# PROC051C_LC_Filtering_Reference.net
KiCad netlist of a schematic drawn in Altium Designer
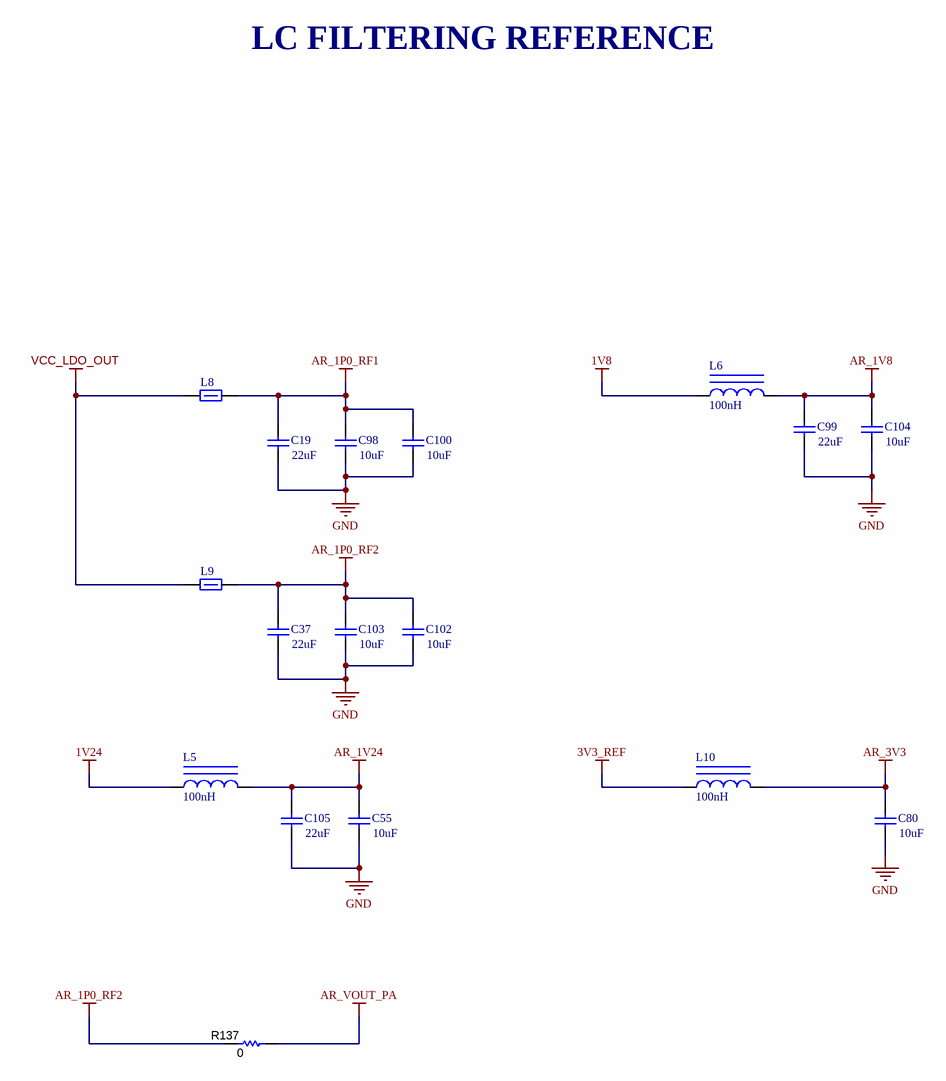
[diagram p0: PROC051C_LC_Filtering_Reference.SchDoc]

(export (version "E")
  (design (tool "Eeschema 10.0.6"))
  (components
    (comp (ref "C19")
      (value "CGA5L1X7R0J226M160AC")
      (footprint "1206_180")
      (description "CAP, CERM, 22 uF, 6.3 V, +/- 10%, X7R, AEC-Q200 Grade 1, 1206")
      (fields
        (field (name "MANUFACTURER") "TDK")
        (field (name "VALUEDISPLAYED") "22uF")
        (field (name "PUBLISHER") "Texas Instruments")
      )
      (libsource (lib "Altium Vault - TI") (part "Capacitor"))
    )
    (comp (ref "C37")
      (value "CGA5L1X7R0J226M160AC")
      (footprint "1206_180")
      (description "CAP, CERM, 22 uF, 6.3 V, +/- 10%, X7R, AEC-Q200 Grade 1, 1206")
      (fields
        (field (name "MANUFACTURER") "TDK")
        (field (name "VALUEDISPLAYED") "22uF")
        (field (name "PUBLISHER") "Texas Instruments")
      )
      (libsource (lib "Altium Vault - TI") (part "Capacitor"))
    )
    (comp (ref "C55")
      (value "GCM21BR71A106KE22L")
      (footprint "0805_HV")
      (description "CAP, CERM, 10 uF, 10 V, +/- 10%, X7R, 0805")
      (fields
        (field (name "MANUFACTURER") "MuRata")
        (field (name "VALUEDISPLAYED") "10uF")
        (field (name "PUBLISHER") "Texas Instruments")
      )
      (libsource (lib "Altium Vault - TI") (part "Capacitor"))
    )
    (comp (ref "C80")
      (value "GCM21BR71A106KE22L")
      (footprint "0805_HV")
      (description "CAP, CERM, 10 uF, 10 V, +/- 10%, X7R, 0805")
      (fields
        (field (name "MANUFACTURER") "MuRata")
        (field (name "VALUEDISPLAYED") "10uF")
        (field (name "PUBLISHER") "Texas Instruments")
      )
      (libsource (lib "Altium Vault - TI") (part "Capacitor"))
    )
    (comp (ref "C98")
      (value "GCM21BR71A106KE22L")
      (footprint "0805_HV")
      (description "CAP, CERM, 10 uF, 10 V, +/- 10%, X7R, 0805")
      (fields
        (field (name "MANUFACTURER") "MuRata")
        (field (name "VALUEDISPLAYED") "10uF")
        (field (name "PUBLISHER") "Texas Instruments")
      )
      (libsource (lib "Altium Vault - TI") (part "Capacitor"))
    )
    (comp (ref "C99")
      (value "CGA5L1X7R0J226M160AC")
      (footprint "1206_180")
      (description "CAP, CERM, 22 uF, 6.3 V, +/- 10%, X7R, AEC-Q200 Grade 1, 1206")
      (fields
        (field (name "MANUFACTURER") "TDK")
        (field (name "VALUEDISPLAYED") "22uF")
        (field (name "PUBLISHER") "Texas Instruments")
      )
      (libsource (lib "Altium Vault - TI") (part "Capacitor"))
    )
    (comp (ref "C100")
      (value "GCM21BR71A106KE22L")
      (footprint "0805_HV")
      (description "CAP, CERM, 10 uF, 10 V, +/- 10%, X7R, 0805")
      (fields
        (field (name "MANUFACTURER") "MuRata")
        (field (name "VALUEDISPLAYED") "10uF")
        (field (name "PUBLISHER") "Texas Instruments")
      )
      (libsource (lib "Altium Vault - TI") (part "Capacitor"))
    )
    (comp (ref "C102")
      (value "GCM21BR71A106KE22L")
      (footprint "0805_HV")
      (description "CAP, CERM, 10 uF, 10 V, +/- 10%, X7R, 0805")
      (fields
        (field (name "MANUFACTURER") "MuRata")
        (field (name "VALUEDISPLAYED") "10uF")
        (field (name "PUBLISHER") "Texas Instruments")
      )
      (libsource (lib "Altium Vault - TI") (part "Capacitor"))
    )
    (comp (ref "C103")
      (value "GCM21BR71A106KE22L")
      (footprint "0805_HV")
      (description "CAP, CERM, 10 uF, 10 V, +/- 10%, X7R, 0805")
      (fields
        (field (name "MANUFACTURER") "MuRata")
        (field (name "VALUEDISPLAYED") "10uF")
        (field (name "PUBLISHER") "Texas Instruments")
      )
      (libsource (lib "Altium Vault - TI") (part "Capacitor"))
    )
    (comp (ref "C104")
      (value "GCM21BR71A106KE22L")
      (footprint "0805_HV")
      (description "CAP, CERM, 10 uF, 10 V, +/- 10%, X7R, 0805")
      (fields
        (field (name "MANUFACTURER") "MuRata")
        (field (name "VALUEDISPLAYED") "10uF")
        (field (name "PUBLISHER") "Texas Instruments")
      )
      (libsource (lib "Altium Vault - TI") (part "Capacitor"))
    )
    (comp (ref "C105")
      (value "CGA5L1X7R0J226M160AC")
      (footprint "1206_180")
      (description "CAP, CERM, 22 uF, 6.3 V, +/- 10%, X7R, AEC-Q200 Grade 1, 1206")
      (fields
        (field (name "MANUFACTURER") "TDK")
        (field (name "VALUEDISPLAYED") "22uF")
        (field (name "PUBLISHER") "Texas Instruments")
      )
      (libsource (lib "Altium Vault - TI") (part "Capacitor"))
    )
    (comp (ref "L5")
      (value "NLCV32T-R10M-EFRD")
      (footprint "NLCV32")
      (description "Inductor, Wirewound, Ferrite, 100 nH, 2.85 A, 0.024 ohm, AEC-Q200 Grade 1, SMD")
      (fields (field (name "MANUFACTURER") "TDK") (field (name "VALUEDISPLAYED") "100nH"))
      (libsource (lib "Altium Vault - TI") (part "Inductor_Iron"))
    )
    (comp (ref "L6")
      (value "NLCV32T-R10M-EFRD")
      (footprint "NLCV32")
      (description "Inductor, Wirewound, Ferrite, 100 nH, 2.85 A, 0.024 ohm, AEC-Q200 Grade 1, SMD")
      (fields (field (name "MANUFACTURER") "TDK") (field (name "VALUEDISPLAYED") "100nH"))
      (libsource (lib "Altium Vault - TI") (part "Inductor_Iron"))
    )
    (comp (ref "L8")
      (value "BLM18KG121TH1D")
      (footprint "0603")
      (description "Ferrite Bead, 120 ohm @ 100 MHz, 1.9 A, 0603")
      (fields (field (name "MANUFACTURER") "MuRata"))
      (libsource (lib "Altium Vault - TI") (part "CMP-0077879-2"))
    )
    (comp (ref "L9")
      (value "BLM18KG121TH1D")
      (footprint "0603")
      (description "Ferrite Bead, 120 ohm @ 100 MHz, 1.9 A, 0603")
      (fields (field (name "MANUFACTURER") "MuRata"))
      (libsource (lib "Altium Vault - TI") (part "Ferrite_Bead"))
    )
    (comp (ref "L10")
      (value "NLCV32T-R10M-EFRD")
      (footprint "NLCV32")
      (description "Inductor, Wirewound, Ferrite, 100 nH, 2.85 A, 0.024 ohm, AEC-Q200 Grade 1, SMD")
      (fields (field (name "MANUFACTURER") "TDK") (field (name "VALUEDISPLAYED") "100nH"))
      (libsource (lib "Altium Vault - TI") (part "Inductor_Iron"))
    )
    (comp (ref "R137")
      (value "MCT06030Z0000ZP500")
      (footprint "0603")
      (description "RES, 0, 5%, 0.125 W, 0603")
      (fields
        (field (name "MANUFACTURER") "Vishay/Beyschlag")
        (field (name "VALUEDISPLAYED") "0")
        (field (name "PUBLISHER") "Texas Instruments")
      )
      (libsource (lib "Altium Vault - TI") (part "CMP-0025884-3"))
    )
  )
  (nets
    (net (code "1") (name "1V8") (class "Default")
      (node (ref "L6") (pin "1") (pinfunction "1_1") (pintype "passive"))
    )
    (net (code "2") (name "1V24") (class "Default")
      (node (ref "L5") (pin "1") (pinfunction "1_1") (pintype "passive"))
    )
    (net (code "3") (name "3V3_REF") (class "Default")
      (node (ref "L10") (pin "1") (pinfunction "1_1") (pintype "passive"))
    )
    (net (code "4") (name "AR_1P0_RF1") (class "Default")
      (node (ref "C100") (pin "1") (pinfunction "1_1") (pintype "passive"))
      (node (ref "C19") (pin "1") (pinfunction "1_1") (pintype "passive"))
      (node (ref "C98") (pin "1") (pinfunction "1_1") (pintype "passive"))
      (node (ref "L8") (pin "2") (pinfunction "2_2") (pintype "passive"))
    )
    (net (code "5") (name "AR_1P0_RF2") (class "Default")
      (node (ref "C102") (pin "1") (pinfunction "1_1") (pintype "passive"))
      (node (ref "C103") (pin "1") (pinfunction "1_1") (pintype "passive"))
      (node (ref "C37") (pin "1") (pinfunction "1_1") (pintype "passive"))
      (node (ref "L9") (pin "2") (pinfunction "2_2") (pintype "passive"))
      (node (ref "R137") (pin "1") (pinfunction "1_1") (pintype "passive"))
    )
    (net (code "6") (name "AR_1V8") (class "Default")
      (node (ref "C104") (pin "1") (pinfunction "1_1") (pintype "passive"))
      (node (ref "C99") (pin "1") (pinfunction "1_1") (pintype "passive"))
      (node (ref "L6") (pin "2") (pinfunction "2_2") (pintype "passive"))
    )
    (net (code "7") (name "AR_1V24") (class "Default")
      (node (ref "C105") (pin "1") (pinfunction "1_1") (pintype "passive"))
      (node (ref "C55") (pin "1") (pinfunction "1_1") (pintype "passive"))
      (node (ref "L5") (pin "2") (pinfunction "2_2") (pintype "passive"))
    )
    (net (code "8") (name "AR_3V3") (class "Default")
      (node (ref "C80") (pin "1") (pinfunction "1_1") (pintype "passive"))
      (node (ref "L10") (pin "2") (pinfunction "2_2") (pintype "passive"))
    )
    (net (code "9") (name "AR_VOUT_PA") (class "Default")
      (node (ref "R137") (pin "2") (pinfunction "2_2") (pintype "passive"))
    )
    (net (code "10") (name "GND") (class "Default")
      (node (ref "C100") (pin "2") (pinfunction "2_2") (pintype "passive"))
      (node (ref "C102") (pin "2") (pinfunction "2_2") (pintype "passive"))
      (node (ref "C103") (pin "2") (pinfunction "2_2") (pintype "passive"))
      (node (ref "C104") (pin "2") (pinfunction "2_2") (pintype "passive"))
      (node (ref "C105") (pin "2") (pinfunction "2_2") (pintype "passive"))
      (node (ref "C19") (pin "2") (pinfunction "2_2") (pintype "passive"))
      (node (ref "C37") (pin "2") (pinfunction "2_2") (pintype "passive"))
      (node (ref "C55") (pin "2") (pinfunction "2_2") (pintype "passive"))
      (node (ref "C80") (pin "2") (pinfunction "2_2") (pintype "passive"))
      (node (ref "C98") (pin "2") (pinfunction "2_2") (pintype "passive"))
      (node (ref "C99") (pin "2") (pinfunction "2_2") (pintype "passive"))
    )
    (net (code "11") (name "VCC_LDO_OUT") (class "Default")
      (node (ref "L8") (pin "1") (pinfunction "1_1") (pintype "passive"))
      (node (ref "L9") (pin "1") (pinfunction "1_1") (pintype "passive"))
    )
  )
)
